# Servo_CB_Upgrade.net
KiCad netlist of a schematic drawn in Altium Designer
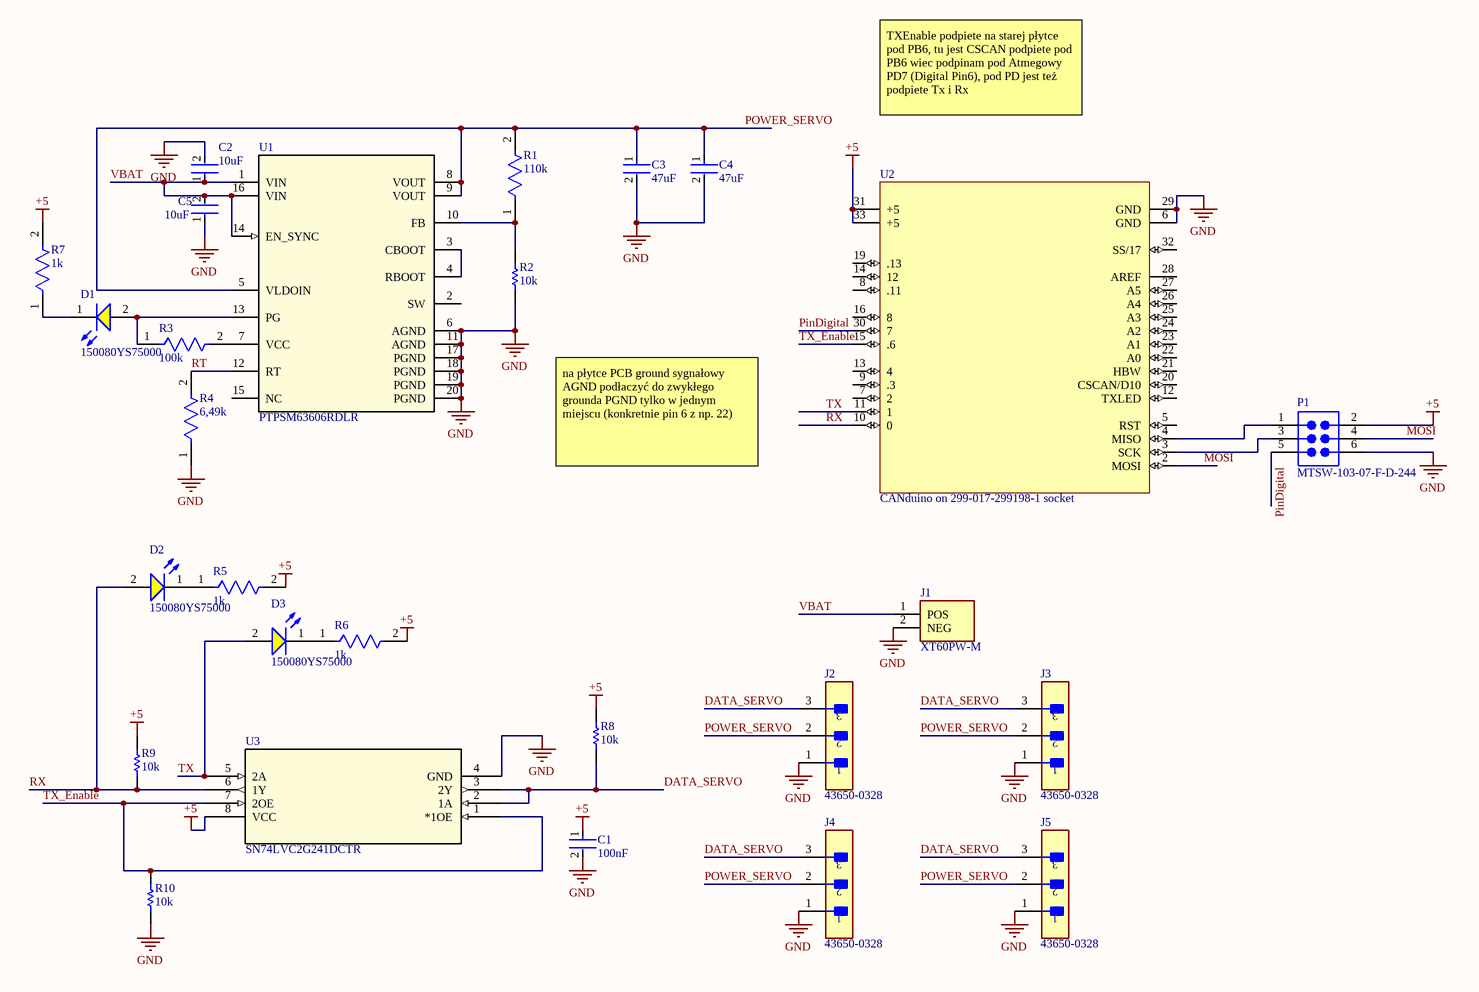
[diagram p0: Servo CB Upgrade.SchDoc]

(export (version "E")
  (design (tool "Eeschema 10.0.6"))
  (components
    (comp (ref "C1")
      (value "100nF")
      (footprint "FP-0805-L_2_01_0_2-W_1_25-IPC_B")
      (description "Automotive Ceramic Capacitor, 0805, 100nF, 10%, X7R, 15%, 100V")
      (fields (field (name "TOLERANCE") "10%") (field (name "VOLTAGE") "100V"))
      (libsource (lib "Altium Content Vault") (part "b4654b650e69147ec39a6b967a45e02"))
    )
    (comp (ref "C2")
      (value "10uF")
      (footprint "FP-CL32-IPC_C")
      (description "Cap Ceramic 10uF 35V X7R ±10% SMD 1210 +125°C Embossed T/R")
      (fields (field (name "VOLTAGE") "35V") (field (name "TOLERANCE") "10%"))
      (libsource (lib "Altium Content Vault") (part "b4654b650e69147ec39a6b967a45e02"))
    )
    (comp (ref "C3")
      (value "47uF")
      (footprint "FP-GRM32E-0_3-0_2-IPC_A")
      (description "Chip Multilayer Ceramic Capacitors for General Purpose, 1210, 47uF, X6S, 22%, 10%, 16V")
      (fields (field (name "VOLTAGE") "16V") (field (name "TOLERANCE") "10%"))
      (libsource (lib "Altium Content Vault") (part "02cd4be3c70576c341d710602a673aa"))
    )
    (comp (ref "C4")
      (value "47uF")
      (footprint "FP-GRM32E-0_3-0_2-IPC_A")
      (description "Chip Multilayer Ceramic Capacitors for General Purpose, 1210, 47uF, X6S, 22%, 10%, 16V")
      (fields (field (name "VOLTAGE") "16V") (field (name "TOLERANCE") "10%"))
      (libsource (lib "Altium Content Vault") (part "02cd4be3c70576c341d710602a673aa"))
    )
    (comp (ref "C5")
      (value "10uF")
      (footprint "FP-CL32-IPC_C")
      (description "Cap Ceramic 10uF 35V X7R ±10% SMD 1210 +125°C Embossed T/R")
      (fields (field (name "VOLTAGE") "35V") (field (name "TOLERANCE") "10%"))
      (libsource (lib "Altium Content Vault") (part "b4654b650e69147ec39a6b967a45e02"))
    )
    (comp (ref "D1")
      (value "150080YS75000")
      (footprint "WL-SMCW_0805_150080xx75000")
      (description "2 V Yellow LED 2012 (0805) SMD, Wurth Elektronik WL-SMCW 150080YS75000")
      (libsource (lib "Altium Content Vault") (part "LED_Yellow_2A-1K"))
    )
    (comp (ref "D2")
      (value "150080YS75000")
      (footprint "WL-SMCW_0805_150080xx75000")
      (description "2 V Yellow LED 2012 (0805) SMD, Wurth Elektronik WL-SMCW 150080YS75000")
      (libsource (lib "Altium Content Vault") (part "LED_Yellow_2A-1K"))
    )
    (comp (ref "D3")
      (value "150080YS75000")
      (footprint "WL-SMCW_0805_150080xx75000")
      (description "2 V Yellow LED 2012 (0805) SMD, Wurth Elektronik WL-SMCW 150080YS75000")
      (libsource (lib "Altium Content Vault") (part "LED_Yellow_2A-1K"))
    )
    (comp (ref "J1")
      (value "XT60PW-M")
      (footprint "AMASS_XT60PW-M:AMASS_XT60PW-M")
      (description "Socket, DC supply, male, PIN: 2")
      (fields (field (name "MF") "AMASS"))
      (libsource (lib "XT60PW-M") (part "XT60PW-M"))
    )
    (comp (ref "J2")
      (value "43650-0328")
      (footprint "FP-43650-0328-MFG")
      (description "43650-0328 Connector Header HDR 3 POS 3mm Solder ST Thru-Hole 3 Terminal 1 Port Micro-Fit 3.0 Tray")
      (libsource (lib "Altium Content Vault") (part "0d3f023dd272f625e17a2be33dea85f"))
    )
    (comp (ref "J3")
      (value "43650-0328")
      (footprint "FP-43650-0328-MFG")
      (description "43650-0328 Connector Header HDR 3 POS 3mm Solder ST Thru-Hole 3 Terminal 1 Port Micro-Fit 3.0 Tray")
      (libsource (lib "Altium Content Vault") (part "0d3f023dd272f625e17a2be33dea85f"))
    )
    (comp (ref "J4")
      (value "43650-0328")
      (footprint "FP-43650-0328-MFG")
      (description "43650-0328 Connector Header HDR 3 POS 3mm Solder ST Thru-Hole 3 Terminal 1 Port Micro-Fit 3.0 Tray")
      (libsource (lib "Altium Content Vault") (part "0d3f023dd272f625e17a2be33dea85f"))
    )
    (comp (ref "J5")
      (value "43650-0328")
      (footprint "FP-43650-0328-MFG")
      (description "43650-0328 Connector Header HDR 3 POS 3mm Solder ST Thru-Hole 3 Terminal 1 Port Micro-Fit 3.0 Tray")
      (libsource (lib "Altium Content Vault") (part "0d3f023dd272f625e17a2be33dea85f"))
    )
    (comp (ref "P1")
      (value "MTSW-103-07-F-D-244")
      (footprint "SMTC-MTSW-103-07-X-D-244")
      (fields (field (name "MANUFACTURER") "Samtec"))
      (libsource (lib "Altium Content Vault") (part "SMTC-MTSW-103-07-X-D-244"))
    )
    (comp (ref "R1")
      (value "110k")
      (footprint "FP-AC0603-IPC_A")
      (description "RES 110KΩ 1.00% 0.1W 0603")
      (fields (field (name "TOLERANCE") "1%"))
      (libsource (lib "Altium Content Vault") (part "1029c3af85768c4190bb7ad29bc67b5"))
    )
    (comp (ref "R2")
      (value "10k")
      (footprint "RESC1608X55X25ML10T15")
      (description "Resistor, 10 KOhm, +/- 5%, 100 mW, -55 to 155 degC, 0603 (1608 Metric), RoHS, Tape and Reel")
      (fields (field (name "MANUFACTURER") "Yageo") (field (name "TOLERANCE") "5%"))
      (libsource (lib "Altium Content Vault") (part "RES-2"))
    )
    (comp (ref "R3")
      (value "100k")
      (footprint "FP-AC0603-MFG")
      (description "RES 100KΩ 1.00% 0.1W 0603")
      (fields (field (name "TOLERANCE") "1%"))
      (libsource (lib "Altium Content Vault") (part "1029c3af85768c4190bb7ad29bc67b5"))
    )
    (comp (ref "R4")
      (value "6,49k")
      (footprint "FP-CRCW0603-e3-IPC_A")
      (description "RES Thick Film, 6.49kΩ, 1%, 0.1W, 100ppm/°C, 0603")
      (fields (field (name "TOLERANCE") "1%"))
      (libsource (lib "Altium Content Vault") (part "1029c3af85768c4190bb7ad29bc67b5"))
    )
    (comp (ref "R5")
      (value "1k")
      (footprint "FP-RC0603-0_55-IPC_C")
      (description "RES 1K OHM 1% 1/10W 0603")
      (fields (field (name "TOLERANCE") "1%"))
      (libsource (lib "Altium Content Vault") (part "1029c3af85768c4190bb7ad29bc67b5"))
    )
    (comp (ref "R6")
      (value "1k")
      (footprint "FP-RC0603-0_55-IPC_C")
      (description "RES 1K OHM 1% 1/10W 0603")
      (fields (field (name "TOLERANCE") "1%"))
      (libsource (lib "Altium Content Vault") (part "1029c3af85768c4190bb7ad29bc67b5"))
    )
    (comp (ref "R7")
      (value "1k")
      (footprint "FP-RC0603-0_55-IPC_C")
      (description "RES 1K OHM 1% 1/10W 0603")
      (fields (field (name "TOLERANCE") "1%"))
      (libsource (lib "Altium Content Vault") (part "1029c3af85768c4190bb7ad29bc67b5"))
    )
    (comp (ref "R8")
      (value "10k")
      (footprint "RESC1608X55X25ML10T15")
      (description "Resistor, 10 KOhm, +/- 5%, 100 mW, -55 to 155 degC, 0603 (1608 Metric), RoHS, Tape and Reel")
      (fields (field (name "MANUFACTURER") "Yageo") (field (name "TOLERANCE") "5%"))
      (libsource (lib "Altium Content Vault") (part "RES-2"))
    )
    (comp (ref "R9")
      (value "10k")
      (footprint "RESC1608X55X25ML10T15")
      (description "Resistor, 10 KOhm, +/- 5%, 100 mW, -55 to 155 degC, 0603 (1608 Metric), RoHS, Tape and Reel")
      (fields (field (name "MANUFACTURER") "Yageo") (field (name "TOLERANCE") "5%"))
      (libsource (lib "Altium Content Vault") (part "RES-2"))
    )
    (comp (ref "R10")
      (value "10k")
      (footprint "RESC1608X55X25ML10T15")
      (description "Resistor, 10 KOhm, +/- 5%, 100 mW, -55 to 155 degC, 0603 (1608 Metric), RoHS, Tape and Reel")
      (fields (field (name "MANUFACTURER") "Yageo") (field (name "TOLERANCE") "5%"))
      (libsource (lib "Altium Content Vault") (part "RES-2"))
    )
    (comp (ref "U1")
      (value "PTPSM63606RDLR")
      (footprint "RDL0020A-MFG")
      (description "No Description Available")
      (libsource (lib "PTPSM63606RDLR") (part "PTPSM63606RDLR"))
    )
    (comp (ref "U2")
      (value "CANduino on 299-017-299198-1 socket")
      (footprint "CANduino on 299-017-299198-1 socket")
      (description "CANduino board without pins 1, 17, 18 and 34 due to socket specification")
      (libsource (lib "CANduino") (part "CANduino on 299-017-299198-1 socket"))
    )
    (comp (ref "U3")
      (value "SN74LVC2G241DCTR")
      (footprint "DCT8")
      (description "No Description Available")
      (libsource (lib "SN74LVC2G241DCTR") (part "SN74LVC2G241DCTR"))
    )
  )
  (nets
    (net (code "1") (name "+5") (class "Default")
      (node (ref "C1") (pin "1") (pinfunction "1_1") (pintype "passive"))
      (node (ref "P1") (pin "2") (pinfunction "2_2") (pintype "passive"))
      (node (ref "R5") (pin "2") (pinfunction "2_2") (pintype "passive"))
      (node (ref "R6") (pin "2") (pinfunction "2_2") (pintype "passive"))
      (node (ref "R7") (pin "2") (pinfunction "2_2") (pintype "passive"))
      (node (ref "R8") (pin "2") (pinfunction "2_2") (pintype "passive"))
      (node (ref "R9") (pin "2") (pinfunction "2_2") (pintype "passive"))
      (node (ref "U2") (pin "31") (pinfunction "+5_31") (pintype "power_in"))
      (node (ref "U2") (pin "33") (pinfunction "+5_33") (pintype "power_in"))
      (node (ref "U3") (pin "8") (pinfunction "VCC_8") (pintype "power_in"))
    )
    (net (code "2") (name "/DATA_SERVO") (class "Default")
      (node (ref "J2") (pin "3") (pinfunction "3_3") (pintype "passive"))
      (node (ref "J3") (pin "3") (pinfunction "3_3") (pintype "passive"))
      (node (ref "J4") (pin "3") (pinfunction "3_3") (pintype "passive"))
      (node (ref "J5") (pin "3") (pinfunction "3_3") (pintype "passive"))
      (node (ref "R8") (pin "1") (pinfunction "1_1") (pintype "passive"))
      (node (ref "U3") (pin "2") (pinfunction "1A_2") (pintype "input"))
      (node (ref "U3") (pin "3") (pinfunction "2Y_3") (pintype "output"))
    )
    (net (code "3") (name "/MOSI") (class "Default")
      (node (ref "P1") (pin "4") (pinfunction "4_4") (pintype "passive"))
      (node (ref "U2") (pin "2") (pinfunction "MOSI_2") (pintype "bidirectional"))
    )
    (net (code "4") (name "/POWER_SERVO") (class "Default")
      (node (ref "C3") (pin "1") (pinfunction "1_1") (pintype "passive"))
      (node (ref "C4") (pin "1") (pinfunction "1_1") (pintype "passive"))
      (node (ref "J2") (pin "2") (pinfunction "2_2") (pintype "passive"))
      (node (ref "J3") (pin "2") (pinfunction "2_2") (pintype "passive"))
      (node (ref "J4") (pin "2") (pinfunction "2_2") (pintype "passive"))
      (node (ref "J5") (pin "2") (pinfunction "2_2") (pintype "passive"))
      (node (ref "R1") (pin "2") (pinfunction "2_2") (pintype "passive"))
      (node (ref "U1") (pin "5") (pinfunction "VLDOIN_5") (pintype "passive"))
      (node (ref "U1") (pin "8") (pinfunction "VOUT_8") (pintype "passive"))
      (node (ref "U1") (pin "9") (pinfunction "VOUT_9") (pintype "passive"))
    )
    (net (code "5") (name "/PinDigital") (class "Default")
      (node (ref "P1") (pin "5") (pinfunction "5_5") (pintype "passive"))
      (node (ref "U2") (pin "30") (pinfunction "7_30") (pintype "bidirectional"))
    )
    (net (code "6") (name "/RT") (class "Default")
      (node (ref "R4") (pin "2") (pinfunction "2_2") (pintype "passive"))
      (node (ref "U1") (pin "12") (pinfunction "RT_12") (pintype "passive"))
    )
    (net (code "7") (name "/RX") (class "Default")
      (node (ref "D2") (pin "2") (pinfunction "A_2") (pintype "passive"))
      (node (ref "R9") (pin "1") (pinfunction "1_1") (pintype "passive"))
      (node (ref "U2") (pin "10") (pinfunction "0_10") (pintype "bidirectional"))
      (node (ref "U3") (pin "6") (pinfunction "1Y_6") (pintype "output"))
    )
    (net (code "8") (name "/TX") (class "Default")
      (node (ref "D3") (pin "2") (pinfunction "A_2") (pintype "passive"))
      (node (ref "U2") (pin "11") (pinfunction "1_11") (pintype "bidirectional"))
      (node (ref "U3") (pin "5") (pinfunction "2A_5") (pintype "input"))
    )
    (net (code "9") (name "/TX_Enable") (class "Default")
      (node (ref "R10") (pin "2") (pinfunction "2_2") (pintype "passive"))
      (node (ref "U2") (pin "15") (pinfunction ".6_15") (pintype "bidirectional"))
      (node (ref "U3") (pin "1") (pinfunction "*1OE_1") (pintype "input"))
      (node (ref "U3") (pin "7") (pinfunction "2OE_7") (pintype "input"))
    )
    (net (code "10") (name "/VBAT") (class "Default")
      (node (ref "C2") (pin "1") (pinfunction "1_1") (pintype "passive"))
      (node (ref "C5") (pin "2") (pinfunction "2_2") (pintype "passive"))
      (node (ref "J1") (pin "1") (pinfunction "POS_1") (pintype "passive"))
      (node (ref "U1") (pin "1") (pinfunction "VIN_1") (pintype "power_in"))
      (node (ref "U1") (pin "14") (pinfunction "EN_SYNC_14") (pintype "input"))
      (node (ref "U1") (pin "16") (pinfunction "VIN_16") (pintype "power_in"))
    )
    (net (code "11") (name "GND") (class "Default")
      (node (ref "C1") (pin "2") (pinfunction "2_2") (pintype "passive"))
      (node (ref "C2") (pin "2") (pinfunction "2_2") (pintype "passive"))
      (node (ref "C3") (pin "2") (pinfunction "2_2") (pintype "passive"))
      (node (ref "C4") (pin "2") (pinfunction "2_2") (pintype "passive"))
      (node (ref "C5") (pin "1") (pinfunction "1_1") (pintype "passive"))
      (node (ref "J1") (pin "2") (pinfunction "NEG_2") (pintype "passive"))
      (node (ref "J2") (pin "1") (pinfunction "1_1") (pintype "passive"))
      (node (ref "J3") (pin "1") (pinfunction "1_1") (pintype "passive"))
      (node (ref "J4") (pin "1") (pinfunction "1_1") (pintype "passive"))
      (node (ref "J5") (pin "1") (pinfunction "1_1") (pintype "passive"))
      (node (ref "P1") (pin "6") (pinfunction "6_6") (pintype "passive"))
      (node (ref "R10") (pin "1") (pinfunction "1_1") (pintype "passive"))
      (node (ref "R2") (pin "1") (pinfunction "1_1") (pintype "passive"))
      (node (ref "R4") (pin "1") (pinfunction "1_1") (pintype "passive"))
      (node (ref "U1") (pin "11") (pinfunction "AGND_11") (pintype "power_in"))
      (node (ref "U1") (pin "17") (pinfunction "PGND_17") (pintype "power_in"))
      (node (ref "U1") (pin "18") (pinfunction "PGND_18") (pintype "power_in"))
      (node (ref "U1") (pin "19") (pinfunction "PGND_19") (pintype "power_in"))
      (node (ref "U1") (pin "20") (pinfunction "PGND_20") (pintype "power_in"))
      (node (ref "U1") (pin "6") (pinfunction "AGND_6") (pintype "power_in"))
      (node (ref "U2") (pin "29") (pinfunction "GND_29") (pintype "passive"))
      (node (ref "U2") (pin "6") (pinfunction "GND_6") (pintype "passive"))
      (node (ref "U3") (pin "4") (pinfunction "GND_4") (pintype "power_in"))
    )
    (net (code "12") (name "Net-(D1-A)") (class "Default")
      (node (ref "D1") (pin "2") (pinfunction "A_2") (pintype "passive"))
      (node (ref "R3") (pin "1") (pinfunction "1_1") (pintype "passive"))
      (node (ref "U1") (pin "13") (pinfunction "PG_13") (pintype "open_collector"))
    )
    (net (code "13") (name "Net-(D1-K)") (class "Default")
      (node (ref "D1") (pin "1") (pinfunction "K_1") (pintype "passive"))
      (node (ref "R7") (pin "1") (pinfunction "1_1") (pintype "passive"))
    )
    (net (code "14") (name "Net-(D2-K)") (class "Default")
      (node (ref "D2") (pin "1") (pinfunction "K_1") (pintype "passive"))
      (node (ref "R5") (pin "1") (pinfunction "1_1") (pintype "passive"))
    )
    (net (code "15") (name "Net-(D3-K)") (class "Default")
      (node (ref "D3") (pin "1") (pinfunction "K_1") (pintype "passive"))
      (node (ref "R6") (pin "1") (pinfunction "1_1") (pintype "passive"))
    )
    (net (code "16") (name "Net-(U1-CBOOT)") (class "Default")
      (node (ref "U1") (pin "3") (pinfunction "CBOOT_3") (pintype "passive"))
      (node (ref "U1") (pin "4") (pinfunction "RBOOT_4") (pintype "passive"))
    )
    (net (code "17") (name "Net-(U1-FB)") (class "Default")
      (node (ref "R1") (pin "1") (pinfunction "1_1") (pintype "passive"))
      (node (ref "R2") (pin "2") (pinfunction "2_2") (pintype "passive"))
      (node (ref "U1") (pin "10") (pinfunction "FB_10") (pintype "passive"))
    )
    (net (code "18") (name "Net-(U1-VCC)") (class "Default")
      (node (ref "R3") (pin "2") (pinfunction "2_2") (pintype "passive"))
      (node (ref "U1") (pin "7") (pinfunction "VCC_7") (pintype "passive"))
    )
    (net (code "19") (name "Net-(U2-MISO)") (class "Default")
      (node (ref "P1") (pin "1") (pinfunction "1_1") (pintype "passive"))
      (node (ref "U2") (pin "4") (pinfunction "MISO_4") (pintype "bidirectional"))
    )
    (net (code "20") (name "Net-(U2-SCK)") (class "Default")
      (node (ref "P1") (pin "3") (pinfunction "3_3") (pintype "passive"))
      (node (ref "U2") (pin "3") (pinfunction "SCK_3") (pintype "bidirectional"))
    )
    (net (code "21") (name "unconnected-(U1-NC-Pad15)") (class "Default")
      (node (ref "U1") (pin "15") (pinfunction "NC_15") (pintype "passive"))
    )
    (net (code "22") (name "unconnected-(U1-SW-Pad2)") (class "Default")
      (node (ref "U1") (pin "2") (pinfunction "SW_2") (pintype "passive"))
    )
    (net (code "23") (name "unconnected-(U2-.3-Pad9)") (class "Default")
      (node (ref "U2") (pin "9") (pinfunction ".3_9") (pintype "bidirectional"))
    )
    (net (code "24") (name "unconnected-(U2-.11-Pad8)") (class "Default")
      (node (ref "U2") (pin "8") (pinfunction ".11_8") (pintype "bidirectional"))
    )
    (net (code "25") (name "unconnected-(U2-.13-Pad19)") (class "Default")
      (node (ref "U2") (pin "19") (pinfunction ".13_19") (pintype "bidirectional"))
    )
    (net (code "26") (name "unconnected-(U2-2-Pad7)") (class "Default")
      (node (ref "U2") (pin "7") (pinfunction "2_7") (pintype "bidirectional"))
    )
    (net (code "27") (name "unconnected-(U2-4-Pad13)") (class "Default")
      (node (ref "U2") (pin "13") (pinfunction "4_13") (pintype "bidirectional"))
    )
    (net (code "28") (name "unconnected-(U2-8-Pad16)") (class "Default")
      (node (ref "U2") (pin "16") (pinfunction "8_16") (pintype "bidirectional"))
    )
    (net (code "29") (name "unconnected-(U2-12-Pad14)") (class "Default")
      (node (ref "U2") (pin "14") (pinfunction "12_14") (pintype "bidirectional"))
    )
    (net (code "30") (name "unconnected-(U2-A0-Pad22)") (class "Default")
      (node (ref "U2") (pin "22") (pinfunction "A0_22") (pintype "bidirectional"))
    )
    (net (code "31") (name "unconnected-(U2-A1-Pad23)") (class "Default")
      (node (ref "U2") (pin "23") (pinfunction "A1_23") (pintype "bidirectional"))
    )
    (net (code "32") (name "unconnected-(U2-A2-Pad24)") (class "Default")
      (node (ref "U2") (pin "24") (pinfunction "A2_24") (pintype "bidirectional"))
    )
    (net (code "33") (name "unconnected-(U2-A3-Pad25)") (class "Default")
      (node (ref "U2") (pin "25") (pinfunction "A3_25") (pintype "bidirectional"))
    )
    (net (code "34") (name "unconnected-(U2-A4-Pad26)") (class "Default")
      (node (ref "U2") (pin "26") (pinfunction "A4_26") (pintype "bidirectional"))
    )
    (net (code "35") (name "unconnected-(U2-A5-Pad27)") (class "Default")
      (node (ref "U2") (pin "27") (pinfunction "A5_27") (pintype "bidirectional"))
    )
    (net (code "36") (name "unconnected-(U2-AREF-Pad28)") (class "Default")
      (node (ref "U2") (pin "28") (pinfunction "AREF_28") (pintype "passive"))
    )
    (net (code "37") (name "unconnected-(U2-CSCAN{slash}D10-Pad20)") (class "Default")
      (node (ref "U2") (pin "20") (pinfunction "CSCAN/D10_20") (pintype "bidirectional"))
    )
    (net (code "38") (name "unconnected-(U2-HBW-Pad21)") (class "Default")
      (node (ref "U2") (pin "21") (pinfunction "HBW_21") (pintype "bidirectional"))
    )
    (net (code "39") (name "unconnected-(U2-RST-Pad5)") (class "Default")
      (node (ref "U2") (pin "5") (pinfunction "RST_5") (pintype "bidirectional"))
    )
    (net (code "40") (name "unconnected-(U2-SS{slash}17-Pad32)") (class "Default")
      (node (ref "U2") (pin "32") (pinfunction "SS/17_32") (pintype "bidirectional"))
    )
    (net (code "41") (name "unconnected-(U2-TXLED-Pad12)") (class "Default")
      (node (ref "U2") (pin "12") (pinfunction "TXLED_12") (pintype "bidirectional"))
    )
  )
)
